# teensyAudioXbee_v11.net
KiCad netlist of a schematic drawn in EAGLE
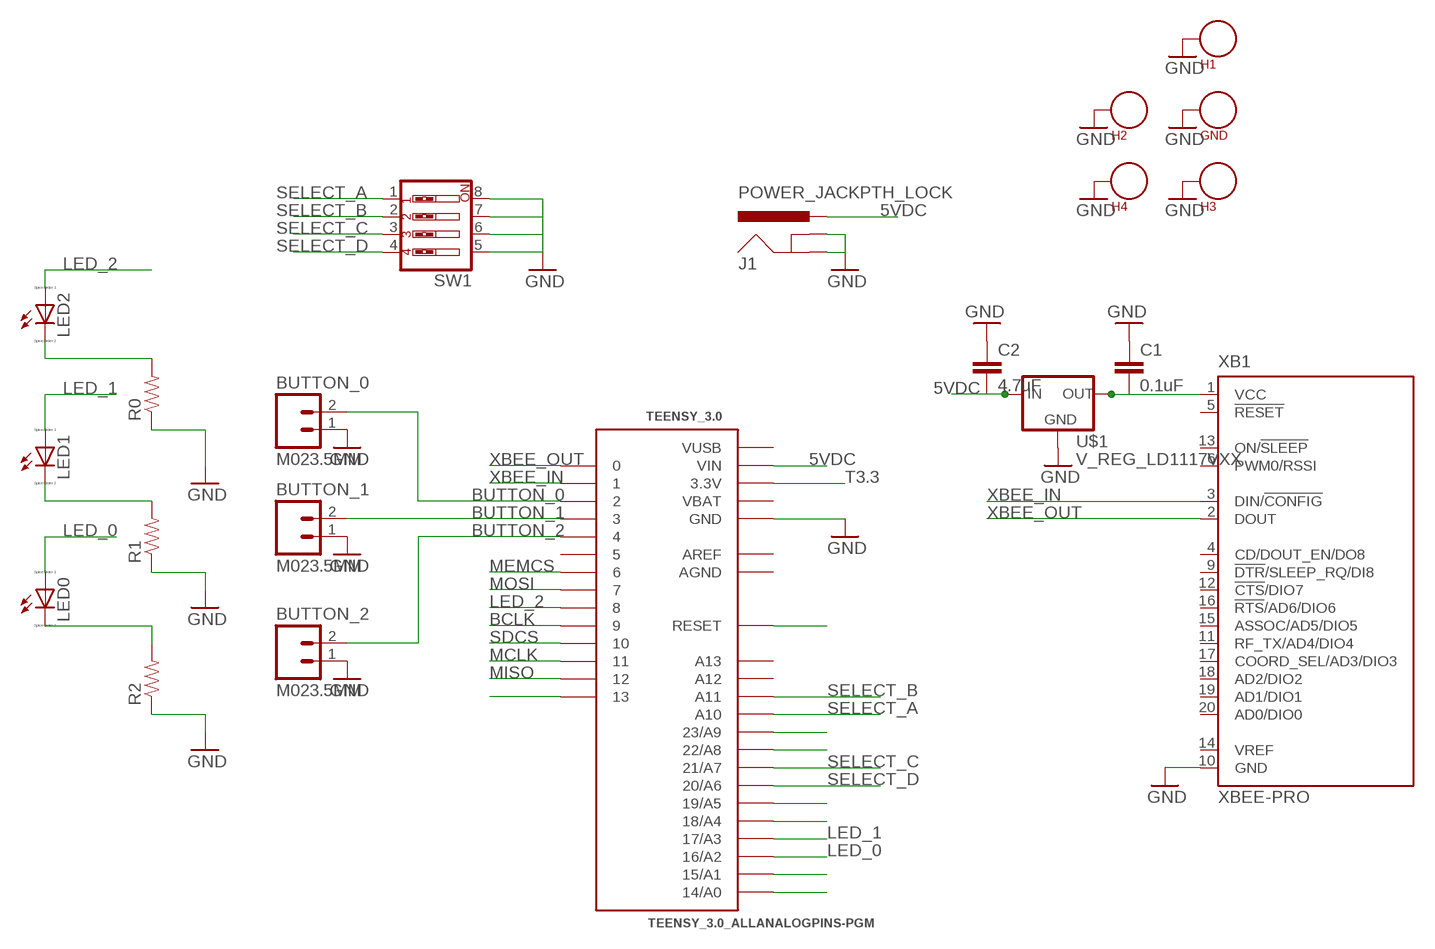
[diagram p0: schematic, sheet 1]

(export (version "E")
  (design (tool "Eeschema 10.0.6"))
  (components
    (comp (ref "BUTTON_0")
      (value "M023.5MM")
      (footprint "eagle-import:SCREWTERMINAL-3.5MM-2")
      (libsource (lib "eagle-import") (part "M023.5MM"))
    )
    (comp (ref "BUTTON_1")
      (value "M023.5MM")
      (footprint "eagle-import:SCREWTERMINAL-3.5MM-2")
      (libsource (lib "eagle-import") (part "M023.5MM"))
    )
    (comp (ref "BUTTON_2")
      (value "M023.5MM")
      (footprint "eagle-import:SCREWTERMINAL-3.5MM-2")
      (libsource (lib "eagle-import") (part "M023.5MM"))
    )
    (comp (ref "C1")
      (value "0.1uF")
      (footprint "eagle-import:CAP-PTH-SMALLEZ")
      (libsource (lib "eagle-import") (part "CAPEZ"))
    )
    (comp (ref "C2")
      (value "4.7uF")
      (footprint "eagle-import:CAP-PTH-SMALLEZ")
      (libsource (lib "eagle-import") (part "CAPEZ"))
    )
    (comp (ref "GND")
      (value "SEW_HOLE")
      (footprint "eagle-import:SIMPLE_HOLE")
      (libsource (lib "eagle-import") (part "SEW_HOLE"))
    )
    (comp (ref "H1")
      (value "SEW_HOLE")
      (footprint "eagle-import:SIMPLE_HOLE")
      (libsource (lib "eagle-import") (part "SEW_HOLE"))
    )
    (comp (ref "H2")
      (value "SEW_HOLE")
      (footprint "eagle-import:SIMPLE_HOLE")
      (libsource (lib "eagle-import") (part "SEW_HOLE"))
    )
    (comp (ref "H3")
      (value "SEW_HOLE")
      (footprint "eagle-import:SIMPLE_HOLE")
      (libsource (lib "eagle-import") (part "SEW_HOLE"))
    )
    (comp (ref "H4")
      (value "SEW_HOLE")
      (footprint "eagle-import:SIMPLE_HOLE")
      (libsource (lib "eagle-import") (part "SEW_HOLE"))
    )
    (comp (ref "J1")
      (value "POWER_JACKPTH_LOCK")
      (footprint "eagle-import:POWER_JACK_PTH_LOCK")
      (libsource (lib "eagle-import") (part "POWER_JACKPTH_LOCK"))
    )
    (comp (ref "LED0")
      (value "LED_ELD260")
      (footprint "eagle-import:LED_LD260")
      (libsource (lib "eagle-import") (part "LED_ELD260"))
    )
    (comp (ref "LED1")
      (value "LED_ELD260")
      (footprint "eagle-import:LED_LD260")
      (libsource (lib "eagle-import") (part "LED_ELD260"))
    )
    (comp (ref "LED2")
      (value "LED_ELD260")
      (footprint "eagle-import:LED_LD260")
      (libsource (lib "eagle-import") (part "LED_ELD260"))
    )
    (comp (ref "R0")
      (value "RESISTORPTH-1/6W")
      (footprint "eagle-import:1_6W-RES")
      (libsource (lib "eagle-import") (part "RESISTORPTH-1/6W"))
    )
    (comp (ref "R1")
      (value "RESISTORPTH-1/6W")
      (footprint "eagle-import:1_6W-RES")
      (libsource (lib "eagle-import") (part "RESISTORPTH-1/6W"))
    )
    (comp (ref "R2")
      (value "RESISTORPTH-1/6W")
      (footprint "eagle-import:1_6W-RES")
      (libsource (lib "eagle-import") (part "RESISTORPTH-1/6W"))
    )
    (comp (ref "SW1")
      (value "SW_DIP-4")
      (footprint "eagle-import:EDG-04")
      (libsource (lib "eagle-import") (part "SW_DIP-4"))
    )
    (comp (ref "TEENSY_3.0")
      (value "TEENSY_3.0_ALLANALOGPINS-PGM")
      (footprint "eagle-import:TEENSY_3.0_ALLANALOG-PGM")
      (libsource (lib "eagle-import") (part "TEENSY_3.0_ALLANALOGPINS-PGM"))
    )
    (comp (ref "U$1")
      (value "V_REG_LD1117VXX")
      (footprint "eagle-import:78XXL")
      (libsource (lib "eagle-import") (part "V_REG_LD1117VXX"))
    )
    (comp (ref "XB1")
      (value "XBEE-PRO")
      (footprint "eagle-import:XBEE-PRO")
      (fields (field (name "MPN") "XBP24-AWI-001"))
      (libsource (lib "eagle-import") (part "XBEE-PRO"))
    )
  )
  (nets
    (net (code "1") (name "/5VDC") (class "Default")
      (node (ref "C2") (pin "2") (pinfunction "2_2") (pintype "passive"))
      (node (ref "J1") (pin "PWR") (pinfunction "PWR_PWR") (pintype "bidirectional"))
      (node (ref "TEENSY_3.0") (pin "VIN") (pinfunction "VIN_VIN") (pintype "power_in"))
      (node (ref "U$1") (pin "OUT") (pinfunction "IN_OUT") (pintype "input"))
    )
    (net (code "2") (name "/AGND") (class "Default")
      (node (ref "TEENSY_3.0") (pin "AGND") (pinfunction "AGND_AGND") (pintype "power_in"))
    )
    (net (code "3") (name "/AREF") (class "Default")
      (node (ref "TEENSY_3.0") (pin "AREF") (pinfunction "AREF_AREF") (pintype "power_in"))
    )
    (net (code "4") (name "/BCLK") (class "Default")
      (node (ref "TEENSY_3.0") (pin "9") (pinfunction "9_9") (pintype "bidirectional"))
    )
    (net (code "5") (name "/BUTTON_0") (class "Default")
      (node (ref "BUTTON_0") (pin "2") (pinfunction "2_2") (pintype "passive"))
      (node (ref "TEENSY_3.0") (pin "2") (pinfunction "2_2") (pintype "bidirectional"))
    )
    (net (code "6") (name "/BUTTON_1") (class "Default")
      (node (ref "BUTTON_1") (pin "2") (pinfunction "2_2") (pintype "passive"))
      (node (ref "TEENSY_3.0") (pin "3") (pinfunction "3_3") (pintype "bidirectional"))
    )
    (net (code "7") (name "/BUTTON_2") (class "Default")
      (node (ref "BUTTON_2") (pin "2") (pinfunction "2_2") (pintype "passive"))
      (node (ref "TEENSY_3.0") (pin "4") (pinfunction "4_4") (pintype "bidirectional"))
    )
    (net (code "8") (name "/LED_0") (class "Default")
      (node (ref "LED0") (pin "A") (pinfunction "A_A") (pintype "passive"))
      (node (ref "TEENSY_3.0") (pin "16/A2") (pinfunction "16/A2_16/A2") (pintype "bidirectional"))
    )
    (net (code "9") (name "/LED_1") (class "Default")
      (node (ref "LED1") (pin "A") (pinfunction "A_A") (pintype "passive"))
      (node (ref "TEENSY_3.0") (pin "17/A3") (pinfunction "17/A3_17/A3") (pintype "bidirectional"))
    )
    (net (code "10") (name "/LED_2") (class "Default")
      (node (ref "LED2") (pin "A") (pinfunction "A_A") (pintype "passive"))
      (node (ref "TEENSY_3.0") (pin "8") (pinfunction "8_8") (pintype "bidirectional"))
    )
    (net (code "11") (name "/MCLK") (class "Default")
      (node (ref "TEENSY_3.0") (pin "11") (pinfunction "11_11") (pintype "bidirectional"))
    )
    (net (code "12") (name "/MEMCS") (class "Default")
      (node (ref "TEENSY_3.0") (pin "6") (pinfunction "6_6") (pintype "bidirectional"))
    )
    (net (code "13") (name "/MISO") (class "Default")
      (node (ref "TEENSY_3.0") (pin "12") (pinfunction "12_12") (pintype "bidirectional"))
    )
    (net (code "14") (name "/MOSI") (class "Default")
      (node (ref "TEENSY_3.0") (pin "7") (pinfunction "7_7") (pintype "bidirectional"))
    )
    (net (code "15") (name "/SDCS") (class "Default")
      (node (ref "TEENSY_3.0") (pin "10") (pinfunction "10_10") (pintype "bidirectional"))
    )
    (net (code "16") (name "/SELECT_A") (class "Default")
      (node (ref "SW1") (pin "1") (pinfunction "1_1") (pintype "passive"))
      (node (ref "TEENSY_3.0") (pin "A10") (pinfunction "A10_A10") (pintype "bidirectional"))
    )
    (net (code "17") (name "/SELECT_B") (class "Default")
      (node (ref "SW1") (pin "2") (pinfunction "2_2") (pintype "passive"))
      (node (ref "TEENSY_3.0") (pin "A11") (pinfunction "A11_A11") (pintype "bidirectional"))
    )
    (net (code "18") (name "/SELECT_C") (class "Default")
      (node (ref "SW1") (pin "3") (pinfunction "3_3") (pintype "passive"))
      (node (ref "TEENSY_3.0") (pin "21/A7") (pinfunction "21/A7_21/A7") (pintype "bidirectional"))
    )
    (net (code "19") (name "/SELECT_D") (class "Default")
      (node (ref "SW1") (pin "4") (pinfunction "4_4") (pintype "passive"))
      (node (ref "TEENSY_3.0") (pin "20/A6") (pinfunction "20/A6_20/A6") (pintype "bidirectional"))
    )
    (net (code "20") (name "/T3.3") (class "Default")
      (node (ref "TEENSY_3.0") (pin "3.3V") (pinfunction "3.3V_3.3V") (pintype "power_in"))
      (node (ref "TEENSY_3.0") (pin "3.3V1") (pinfunction "3.3V_3.3V1") (pintype "power_in"))
      (node (ref "TEENSY_3.0") (pin "3.3V2") (pinfunction "3.3V_3.3V2") (pintype "power_in"))
    )
    (net (code "21") (name "/VBAT") (class "Default")
      (node (ref "TEENSY_3.0") (pin "VBAT") (pinfunction "VBAT_VBAT") (pintype "power_in"))
    )
    (net (code "22") (name "/VUSB") (class "Default")
      (node (ref "TEENSY_3.0") (pin "VUSB") (pinfunction "VUSB_VUSB") (pintype "power_in"))
    )
    (net (code "23") (name "/XBEE_IN") (class "Default")
      (node (ref "TEENSY_3.0") (pin "1") (pinfunction "1_1") (pintype "bidirectional"))
      (node (ref "XB1") (pin "3") (pinfunction "DIN/~{CONFIG}_3") (pintype "input"))
    )
    (net (code "24") (name "/XBEE_OUT") (class "Default")
      (node (ref "TEENSY_3.0") (pin "0") (pinfunction "0_0") (pintype "bidirectional"))
      (node (ref "XB1") (pin "2") (pinfunction "DOUT_2") (pintype "output"))
    )
    (net (code "25") (name "GND") (class "Default")
      (node (ref "BUTTON_0") (pin "1") (pinfunction "1_1") (pintype "passive"))
      (node (ref "BUTTON_1") (pin "1") (pinfunction "1_1") (pintype "passive"))
      (node (ref "BUTTON_2") (pin "1") (pinfunction "1_1") (pintype "passive"))
      (node (ref "C1") (pin "1") (pinfunction "1_1") (pintype "passive"))
      (node (ref "C2") (pin "1") (pinfunction "1_1") (pintype "passive"))
      (node (ref "GND") (pin "P$1") (pinfunction "P$1_P$1") (pintype "bidirectional"))
      (node (ref "H1") (pin "P$1") (pinfunction "P$1_P$1") (pintype "bidirectional"))
      (node (ref "H2") (pin "P$1") (pinfunction "P$1_P$1") (pintype "bidirectional"))
      (node (ref "H3") (pin "P$1") (pinfunction "P$1_P$1") (pintype "bidirectional"))
      (node (ref "H4") (pin "P$1") (pinfunction "P$1_P$1") (pintype "bidirectional"))
      (node (ref "J1") (pin "GND") (pinfunction "GND_GND") (pintype "bidirectional"))
      (node (ref "J1") (pin "GNDBREAK") (pinfunction "GNDBREAK_GNDBREAK") (pintype "bidirectional"))
      (node (ref "R0") (pin "1") (pinfunction "1_1") (pintype "passive"))
      (node (ref "R1") (pin "1") (pinfunction "1_1") (pintype "passive"))
      (node (ref "R2") (pin "1") (pinfunction "1_1") (pintype "passive"))
      (node (ref "SW1") (pin "5") (pinfunction "5_5") (pintype "passive"))
      (node (ref "SW1") (pin "6") (pinfunction "6_6") (pintype "passive"))
      (node (ref "SW1") (pin "7") (pinfunction "7_7") (pintype "passive"))
      (node (ref "SW1") (pin "8") (pinfunction "8_8") (pintype "passive"))
      (node (ref "TEENSY_3.0") (pin "GND") (pinfunction "GND_GND") (pintype "power_in"))
      (node (ref "TEENSY_3.0") (pin "GND1") (pinfunction "GND_GND1") (pintype "power_in"))
      (node (ref "TEENSY_3.0") (pin "GND2") (pinfunction "GND_GND2") (pintype "power_in"))
      (node (ref "U$1") (pin "IN") (pinfunction "GND_IN") (pintype "input"))
      (node (ref "XB1") (pin "10") (pinfunction "GND_10") (pintype "power_in"))
    )
    (net (code "26") (name "Net-(LED0-C)") (class "Default")
      (node (ref "LED0") (pin "K") (pinfunction "C_K") (pintype "passive"))
      (node (ref "R2") (pin "2") (pinfunction "2_2") (pintype "passive"))
    )
    (net (code "27") (name "Net-(LED1-C)") (class "Default")
      (node (ref "LED1") (pin "K") (pinfunction "C_K") (pintype "passive"))
      (node (ref "R1") (pin "2") (pinfunction "2_2") (pintype "passive"))
    )
    (net (code "28") (name "Net-(LED2-C)") (class "Default")
      (node (ref "LED2") (pin "K") (pinfunction "C_K") (pintype "passive"))
      (node (ref "R0") (pin "2") (pinfunction "2_2") (pintype "passive"))
    )
    (net (code "29") (name "Net-(U$1-OUT)") (class "Default")
      (node (ref "C1") (pin "2") (pinfunction "2_2") (pintype "passive"))
      (node (ref "U$1") (pin "GND") (pinfunction "OUT_GND") (pintype "output"))
      (node (ref "XB1") (pin "1") (pinfunction "VCC_1") (pintype "power_in"))
    )
    (net (code "30") (name "unconnected-(TEENSY_3.0-Pad5)") (class "Default")
      (node (ref "TEENSY_3.0") (pin "5") (pinfunction "5_5") (pintype "bidirectional"))
    )
    (net (code "31") (name "unconnected-(TEENSY_3.0-Pad13)") (class "Default")
      (node (ref "TEENSY_3.0") (pin "13") (pinfunction "13_13") (pintype "bidirectional"))
    )
    (net (code "32") (name "unconnected-(TEENSY_3.0-Pad14{slash}A0)") (class "Default")
      (node (ref "TEENSY_3.0") (pin "14/A0") (pinfunction "14/A0_14/A0") (pintype "bidirectional"))
    )
    (net (code "33") (name "unconnected-(TEENSY_3.0-Pad15{slash}A1)") (class "Default")
      (node (ref "TEENSY_3.0") (pin "15/A1") (pinfunction "15/A1_15/A1") (pintype "bidirectional"))
    )
    (net (code "34") (name "unconnected-(TEENSY_3.0-Pad18{slash}A4)") (class "Default")
      (node (ref "TEENSY_3.0") (pin "18/A4") (pinfunction "18/A4_18/A4") (pintype "bidirectional"))
    )
    (net (code "35") (name "unconnected-(TEENSY_3.0-Pad19{slash}A5)") (class "Default")
      (node (ref "TEENSY_3.0") (pin "19/A5") (pinfunction "19/A5_19/A5") (pintype "bidirectional"))
    )
    (net (code "36") (name "unconnected-(TEENSY_3.0-Pad22{slash}A8)") (class "Default")
      (node (ref "TEENSY_3.0") (pin "22/A8") (pinfunction "22/A8_22/A8") (pintype "bidirectional"))
    )
    (net (code "37") (name "unconnected-(TEENSY_3.0-Pad23{slash}A9)") (class "Default")
      (node (ref "TEENSY_3.0") (pin "23/A9") (pinfunction "23/A9_23/A9") (pintype "bidirectional"))
    )
    (net (code "38") (name "unconnected-(TEENSY_3.0-PadA12)") (class "Default")
      (node (ref "TEENSY_3.0") (pin "A12") (pinfunction "A12_A12") (pintype "bidirectional"))
    )
    (net (code "39") (name "unconnected-(TEENSY_3.0-PadA13)") (class "Default")
      (node (ref "TEENSY_3.0") (pin "A13") (pinfunction "A13_A13") (pintype "bidirectional"))
    )
    (net (code "40") (name "unconnected-(TEENSY_3.0-RESET-PadRST)") (class "Default")
      (node (ref "TEENSY_3.0") (pin "RST") (pinfunction "RESET_RST") (pintype "power_in"))
    )
    (net (code "41") (name "unconnected-(XB1-AD0{slash}DIO0-Pad20)") (class "Default")
      (node (ref "XB1") (pin "20") (pinfunction "AD0/DIO0_20") (pintype "bidirectional"))
    )
    (net (code "42") (name "unconnected-(XB1-AD1{slash}DIO1-Pad19)") (class "Default")
      (node (ref "XB1") (pin "19") (pinfunction "AD1/DIO1_19") (pintype "bidirectional"))
    )
    (net (code "43") (name "unconnected-(XB1-AD2{slash}DIO2-Pad18)") (class "Default")
      (node (ref "XB1") (pin "18") (pinfunction "AD2/DIO2_18") (pintype "bidirectional"))
    )
    (net (code "44") (name "unconnected-(XB1-ASSOC{slash}AD5{slash}DIO5-Pad15)") (class "Default")
      (node (ref "XB1") (pin "15") (pinfunction "ASSOC/AD5/DIO5_15") (pintype "bidirectional"))
    )
    (net (code "45") (name "unconnected-(XB1-CD{slash}DOUT_EN{slash}DO8-Pad4)") (class "Default")
      (node (ref "XB1") (pin "4") (pinfunction "CD/DOUT_EN/DO8_4") (pintype "output"))
    )
    (net (code "46") (name "unconnected-(XB1-COORD_SEL{slash}AD3{slash}DIO3-Pad17)") (class "Default")
      (node (ref "XB1") (pin "17") (pinfunction "COORD_SEL/AD3/DIO3_17") (pintype "bidirectional"))
    )
    (net (code "47") (name "unconnected-(XB1-ON{slash}~{SLEEP}-Pad13)") (class "Default")
      (node (ref "XB1") (pin "13") (pinfunction "ON/~{SLEEP}_13") (pintype "output"))
    )
    (net (code "48") (name "unconnected-(XB1-PWM0{slash}RSSI-Pad6)") (class "Default")
      (node (ref "XB1") (pin "6") (pinfunction "PWM0/RSSI_6") (pintype "output"))
    )
    (net (code "49") (name "unconnected-(XB1-RF_TX{slash}AD4{slash}DIO4-Pad11)") (class "Default")
      (node (ref "XB1") (pin "11") (pinfunction "RF_TX/AD4/DIO4_11") (pintype "bidirectional"))
    )
    (net (code "50") (name "unconnected-(XB1-VREF-Pad14)") (class "Default")
      (node (ref "XB1") (pin "14") (pinfunction "VREF_14") (pintype "input"))
    )
    (net (code "51") (name "unconnected-(XB1-~{CTS}{slash}DIO7-Pad12)") (class "Default")
      (node (ref "XB1") (pin "12") (pinfunction "~{CTS}/DIO7_12") (pintype "bidirectional"))
    )
    (net (code "52") (name "unconnected-(XB1-~{DTR}{slash}SLEEP_RQ{slash}DI8-Pad9)") (class "Default")
      (node (ref "XB1") (pin "9") (pinfunction "~{DTR}/SLEEP_RQ/DI8_9") (pintype "bidirectional"))
    )
    (net (code "53") (name "unconnected-(XB1-~{RESET}-Pad5)") (class "Default")
      (node (ref "XB1") (pin "5") (pinfunction "~{RESET}_5") (pintype "input"))
    )
    (net (code "54") (name "unconnected-(XB1-~{RTS}{slash}AD6{slash}DIO6-Pad16)") (class "Default")
      (node (ref "XB1") (pin "16") (pinfunction "~{RTS}/AD6/DIO6_16") (pintype "bidirectional"))
    )
  )
)
